# SI24r1.net
KiCad netlist of a schematic drawn in Altium Designer
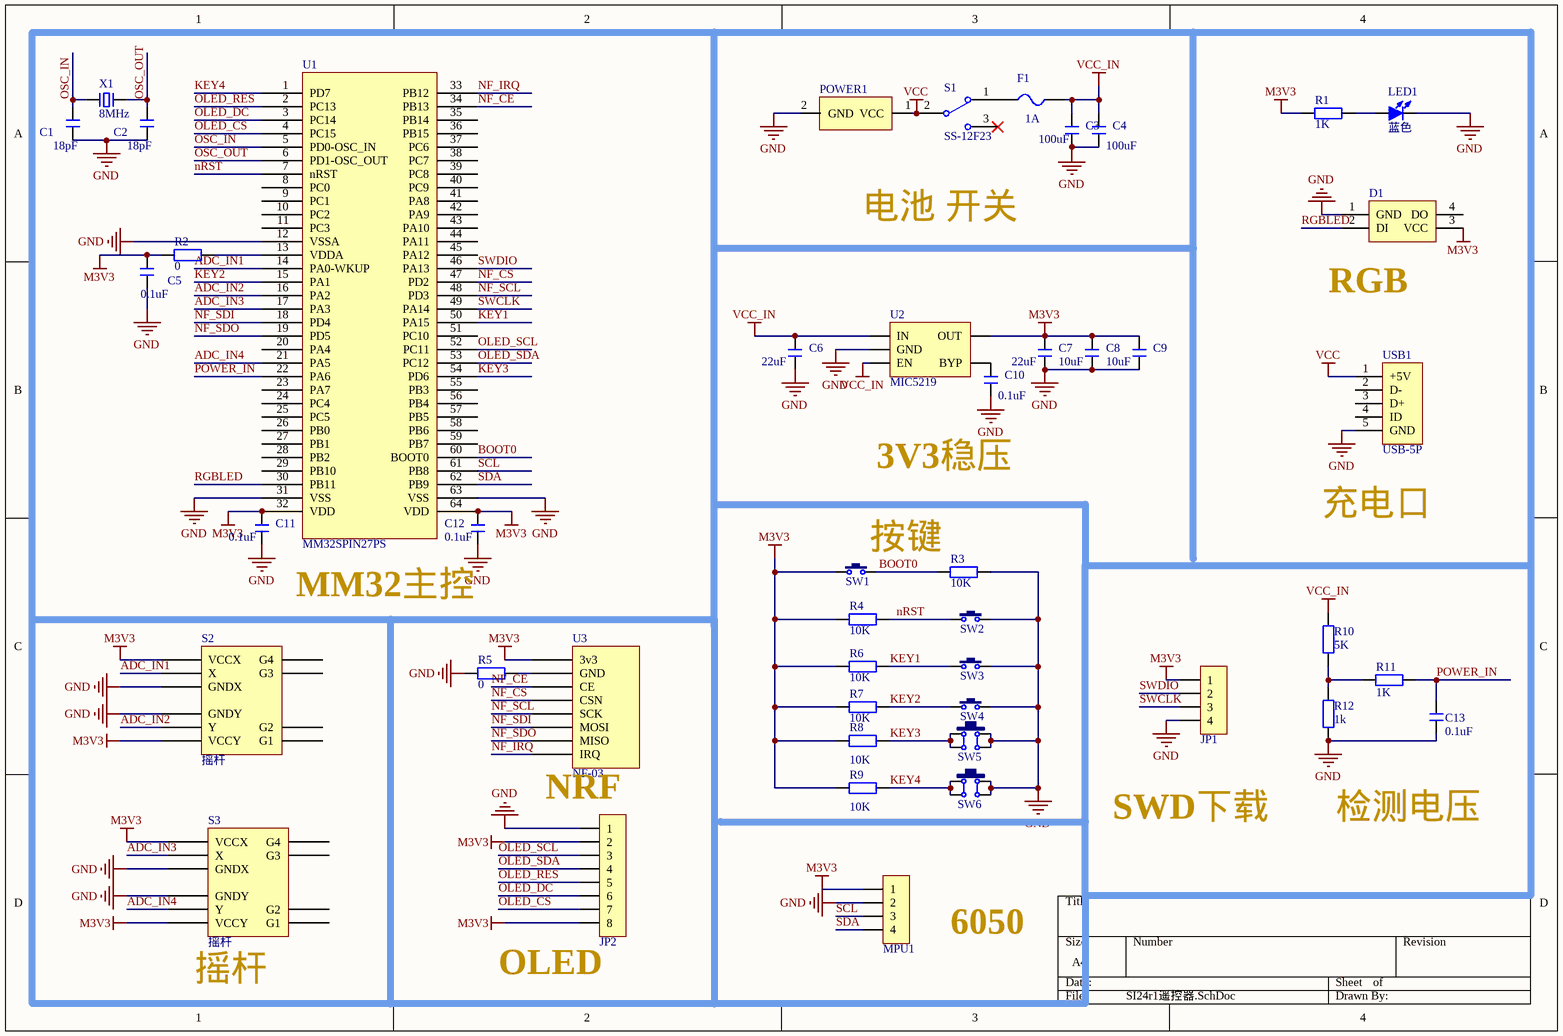
[diagram p0: SI24r1遥控器.SchDoc]

(export (version "E")
  (design (tool "Eeschema 10.0.6"))
  (components
    (comp (ref "C1")
      (value "18pF")
      (footprint "C 0805_M")
      (description "贴片电容")
      (libsource (lib "0.1 - 电阻-电容-电感") (part "C"))
    )
    (comp (ref "C2")
      (value "18pF")
      (footprint "C 0805_M")
      (description "贴片电容")
      (libsource (lib "0.1 - 电阻-电容-电感") (part "C"))
    )
    (comp (ref "C3")
      (value "100uF")
      (footprint "C 0805_M")
      (description "贴片电容")
      (libsource (lib "0.1 - 电阻-电容-电感") (part "C"))
    )
    (comp (ref "C4")
      (value "100uF")
      (footprint "C 0805_M")
      (description "贴片电容")
      (libsource (lib "0.1 - 电阻-电容-电感") (part "C"))
    )
    (comp (ref "C5")
      (value "0.1uF")
      (footprint "C 0805_M")
      (description "贴片电容")
      (libsource (lib "0.1 - 电阻-电容-电感") (part "C"))
    )
    (comp (ref "C6")
      (value "22uF")
      (footprint "C 0805_M")
      (description "贴片电容")
      (libsource (lib "0.1 - 电阻-电容-电感") (part "C"))
    )
    (comp (ref "C7")
      (value "22uF")
      (footprint "C 0805_M")
      (description "贴片电容")
      (libsource (lib "0.1 - 电阻-电容-电感") (part "C"))
    )
    (comp (ref "C8")
      (value "10uF")
      (footprint "C 0805_M")
      (description "贴片电容")
      (libsource (lib "0.1 - 电阻-电容-电感") (part "C"))
    )
    (comp (ref "C9")
      (value "10uF")
      (footprint "C 0805_M")
      (description "贴片电容")
      (libsource (lib "0.1 - 电阻-电容-电感") (part "C"))
    )
    (comp (ref "C10")
      (value "0.1uF")
      (footprint "C 0805_M")
      (description "贴片电容")
      (libsource (lib "0.1 - 电阻-电容-电感") (part "C"))
    )
    (comp (ref "C11")
      (value "0.1uF")
      (footprint "C 0805_M")
      (description "贴片电容")
      (libsource (lib "0.1 - 电阻-电容-电感") (part "C"))
    )
    (comp (ref "C12")
      (value "0.1uF")
      (footprint "C 0805_M")
      (description "贴片电容")
      (libsource (lib "0.1 - 电阻-电容-电感") (part "C"))
    )
    (comp (ref "C13")
      (value "0.1uF")
      (footprint "C 0805_M")
      (description "贴片电容")
      (libsource (lib "0.1 - 电阻-电容-电感") (part "C"))
    )
    (comp (ref "D1")
      (value "P923D")
      (footprint "RGB_LED_5050")
      (fields (field (name "PUBLISHER") "mazhongwei"))
      (libsource (lib "RoboFly") (part "P923D"))
    )
    (comp (ref "F1")
      (value "1A")
      (footprint "FU 0805")
      (description "贴片保险丝")
      (fields (field (name "版权归属") "源创客"))
      (libsource (lib "2.0 - 保险丝-晶振-光耦") (part "FU"))
    )
    (comp (ref "JP1")
      (value "HDR-1X4")
      (footprint "XH2.54-WI-4P")
      (description "4P接插件")
      (fields (field (name "版权归属") "封装库来自淘宝 ID：黄晶宝石"))
      (libsource (lib "5.3 - 接插件-脚距2.54 (100mil) ") (part "Header 4"))
    )
    (comp (ref "JP2")
      (value "HDR-1X8")
      (footprint "IPS")
      (description "8P接插件")
      (fields (field (name "版权归属") "封装库来自淘宝 ID：黄晶宝石"))
      (libsource (lib "5.3 - 接插件-脚距2.54 (100mil) ") (part "Header 8"))
    )
    (comp (ref "LED1")
      (value "蓝色")
      (footprint "LED 0805B")
      (description "贴片LED")
      (fields (field (name "版权归属") "封装库来自淘宝 ID：黄晶宝石"))
      (libsource (lib "0.3 - LED发光二极管") (part "LED-SMD"))
    )
    (comp (ref "MPU1")
      (value "HDR-1X4")
      (footprint "HDR2.54-LI-4P")
      (description "4P接插件")
      (fields (field (name "版权归属") "封装库来自淘宝 ID：黄晶宝石"))
      (libsource (lib "5.3 - 接插件-脚距2.54 (100mil) ") (part "Header 4"))
    )
    (comp (ref "POWER1") (value "~") (footprint "XH2.54-LI-2P") (libsource (lib "原理图库") (part "T槽")))
    (comp (ref "R1")
      (value "1K")
      (footprint "R 0805_M")
      (description "Resistor")
      (fields (field (name "Comment") "Res2") (field (name "PUBLISHER") "Altium Limited"))
      (libsource (lib "") (part "Res2_1"))
    )
    (comp (ref "R2") (value "0") (footprint "R 0805_M") (libsource (lib "") (part "RES_1")))
    (comp (ref "R3") (value "10K") (footprint "R 0805_M") (libsource (lib "飞思卡尔") (part "RES")))
    (comp (ref "R4") (value "10K") (footprint "R 0805_M") (libsource (lib "飞思卡尔") (part "RES")))
    (comp (ref "R5") (value "0") (footprint "R 0805_M") (libsource (lib "") (part "RES_1")))
    (comp (ref "R6") (value "10K") (footprint "R 0805_M") (libsource (lib "飞思卡尔") (part "RES")))
    (comp (ref "R7") (value "10K") (footprint "R 0805_M") (libsource (lib "飞思卡尔") (part "RES")))
    (comp (ref "R8") (value "10K") (footprint "R 0805_M") (libsource (lib "飞思卡尔") (part "RES")))
    (comp (ref "R9") (value "10K") (footprint "R 0805_M") (libsource (lib "飞思卡尔") (part "RES")))
    (comp (ref "R10")
      (value "5K")
      (footprint "R 0805_M")
      (description "Resistor")
      (fields (field (name "Comment") "Res2") (field (name "PUBLISHER") "Altium Limited"))
      (libsource (lib "双电机节能车主板原理图库") (part "Res2"))
    )
    (comp (ref "R11")
      (value "1K")
      (footprint "R 0805_M")
      (description "Resistor")
      (fields (field (name "Comment") "Res2") (field (name "PUBLISHER") "Altium Limited"))
      (libsource (lib "") (part "Res2_1"))
    )
    (comp (ref "R12")
      (value "1k")
      (footprint "R 0805_M")
      (description "Resistor")
      (fields (field (name "Comment") "Res2") (field (name "PUBLISHER") "Altium Limited"))
      (libsource (lib "双电机节能车主板原理图库") (part "Res2"))
    )
    (comp (ref "S1")
      (value "SS-12F23")
      (footprint "SS-12D10")
      (description "1路波动开关")
      (fields (field (name "版权归属") "封装库来自淘宝 ID：黄晶宝石"))
      (libsource (lib "0.7 - 常用按键-开关") (part "SSW-1P"))
    )
    (comp (ref "S2") (value "摇杆") (footprint "3D161摇杆") (libsource (lib "摇杆") (part "摇杆")))
    (comp (ref "S3") (value "摇杆") (footprint "3D161摇杆") (libsource (lib "摇杆") (part "摇杆")))
    (comp (ref "SW1")
      (value "3x6x5")
      (footprint "TSW SMD-3*6*2.5")
      (description "3x6轻触开关")
      (fields (field (name "版权归属") "封装库来自淘宝 ID：黄晶宝石"))
      (libsource (lib "0.7 - 常用按键-开关") (part "TSW 3x6"))
    )
    (comp (ref "SW2")
      (value "3x6x5")
      (footprint "TSW SMD-3*6*2.5")
      (description "3x6轻触开关")
      (fields (field (name "版权归属") "封装库来自淘宝 ID：黄晶宝石"))
      (libsource (lib "0.7 - 常用按键-开关") (part "TSW 3x6"))
    )
    (comp (ref "SW3")
      (value "6x6x5")
      (footprint "TSW DIP-6*6*7_V")
      (description "侧按直插6x6轻触开关")
      (fields (field (name "版权归属") "封装库来自淘宝 ID：黄晶宝石"))
      (libsource (lib "0.7 - 常用按键-开关") (part "TSW DIP-6x6_V"))
    )
    (comp (ref "SW4")
      (value "6x6x5")
      (footprint "TSW DIP-6*6*7_V")
      (description "侧按直插6x6轻触开关")
      (fields (field (name "版权归属") "封装库来自淘宝 ID：黄晶宝石"))
      (libsource (lib "0.7 - 常用按键-开关") (part "TSW DIP-6x6_V"))
    )
    (comp (ref "SW5")
      (value "6x6x5")
      (footprint "TSW DIP-6*6*6")
      (description "直插6x6轻触开关")
      (fields (field (name "版权归属") "封装库来自淘宝 ID：黄晶宝石"))
      (libsource (lib "0.7 - 常用按键-开关") (part "TSW DIP-6x6"))
    )
    (comp (ref "SW6")
      (value "6x6x5")
      (footprint "TSW DIP-6*6*6")
      (description "直插6x6轻触开关")
      (fields (field (name "版权归属") "封装库来自淘宝 ID：黄晶宝石"))
      (libsource (lib "0.7 - 常用按键-开关") (part "TSW DIP-6x6"))
    )
    (comp (ref "U1")
      (value "MM32SPIN27PS")
      (footprint "LQFP64 10x10_M")
      (libsource (lib "STC智能车") (part "MM32SPIN27PS"))
    )
    (comp (ref "U2") (value "MIC5219") (footprint "SOT23-5M") (libsource (lib "TI") (part "MIC5219")))
    (comp (ref "U3") (value "NF-03") (footprint "NF-03") (libsource (lib "摇杆") (part "NF-03")))
    (comp (ref "USB1")
      (value "USB-5P")
      (footprint "USB-MICRO_A")
      (description "微型USB母座")
      (libsource (lib "0.8 - 网口-音频插座") (part "USB-5P"))
    )
    (comp (ref "X1")
      (value "8MHz")
      (footprint "OSC 5032-2P")
      (description "2脚无源脚晶振")
      (fields (field (name "版权归属") "源创客"))
      (libsource (lib "2.0 - 保险丝-晶振-光耦") (part "XTAL-2P"))
    )
  )
  (nets
    (net (code "1") (name "/ADC_IN1") (class "Default")
      (node (ref "S2") (pin "2") (pinfunction "X_2") (pintype "passive"))
      (node (ref "U1") (pin "14") (pinfunction "PA0-WKUP_14") (pintype "passive"))
    )
    (net (code "2") (name "/ADC_IN2") (class "Default")
      (node (ref "S2") (pin "5") (pinfunction "Y_5") (pintype "passive"))
      (node (ref "U1") (pin "16") (pinfunction "PA2_16") (pintype "passive"))
    )
    (net (code "3") (name "/ADC_IN3") (class "Default")
      (node (ref "S3") (pin "2") (pinfunction "X_2") (pintype "passive"))
      (node (ref "U1") (pin "17") (pinfunction "PA3_17") (pintype "passive"))
    )
    (net (code "4") (name "/ADC_IN4") (class "Default")
      (node (ref "S3") (pin "5") (pinfunction "Y_5") (pintype "passive"))
      (node (ref "U1") (pin "21") (pinfunction "PA5_21") (pintype "passive"))
    )
    (net (code "5") (name "/BOOT0") (class "Default")
      (node (ref "R3") (pin "1") (pinfunction "1_1") (pintype "passive"))
      (node (ref "SW1") (pin "2") (pinfunction "2_2") (pintype "passive"))
      (node (ref "U1") (pin "60") (pinfunction "BOOT0_60") (pintype "passive"))
    )
    (net (code "6") (name "/KEY1") (class "Default")
      (node (ref "R6") (pin "2") (pinfunction "2_2") (pintype "passive"))
      (node (ref "SW3") (pin "1") (pinfunction "1_1") (pintype "passive"))
      (node (ref "U1") (pin "50") (pinfunction "PA15_50") (pintype "passive"))
    )
    (net (code "7") (name "/KEY2") (class "Default")
      (node (ref "R7") (pin "2") (pinfunction "2_2") (pintype "passive"))
      (node (ref "SW4") (pin "1") (pinfunction "1_1") (pintype "passive"))
      (node (ref "U1") (pin "15") (pinfunction "PA1_15") (pintype "passive"))
    )
    (net (code "8") (name "/KEY3") (class "Default")
      (node (ref "R8") (pin "2") (pinfunction "2_2") (pintype "passive"))
      (node (ref "SW5") (pin "1") (pinfunction "1_1") (pintype "passive"))
      (node (ref "SW5") (pin "4") (pinfunction "4_4") (pintype "passive"))
      (node (ref "U1") (pin "54") (pinfunction "PD6_54") (pintype "passive"))
    )
    (net (code "9") (name "/KEY4") (class "Default")
      (node (ref "R9") (pin "2") (pinfunction "2_2") (pintype "passive"))
      (node (ref "SW6") (pin "1") (pinfunction "1_1") (pintype "passive"))
      (node (ref "SW6") (pin "4") (pinfunction "4_4") (pintype "passive"))
      (node (ref "U1") (pin "1") (pinfunction "PD7_1") (pintype "passive"))
    )
    (net (code "10") (name "/NF_CE") (class "Default")
      (node (ref "U1") (pin "34") (pinfunction "PB13_34") (pintype "passive"))
      (node (ref "U3") (pin "3") (pinfunction "CE_3") (pintype "passive"))
    )
    (net (code "11") (name "/NF_CS") (class "Default")
      (node (ref "U1") (pin "47") (pinfunction "PD2_47") (pintype "passive"))
      (node (ref "U3") (pin "4") (pinfunction "CSN_4") (pintype "passive"))
    )
    (net (code "12") (name "/NF_IRQ") (class "Default")
      (node (ref "U1") (pin "33") (pinfunction "PB12_33") (pintype "passive"))
      (node (ref "U3") (pin "8") (pinfunction "IRQ_8") (pintype "passive"))
    )
    (net (code "13") (name "/NF_SCL") (class "Default")
      (node (ref "U1") (pin "48") (pinfunction "PD3_48") (pintype "passive"))
      (node (ref "U3") (pin "5") (pinfunction "SCK_5") (pintype "passive"))
    )
    (net (code "14") (name "/NF_SDI") (class "Default")
      (node (ref "U1") (pin "18") (pinfunction "PD4_18") (pintype "passive"))
      (node (ref "U3") (pin "6") (pinfunction "MOSI_6") (pintype "passive"))
    )
    (net (code "15") (name "/NF_SDO") (class "Default")
      (node (ref "U1") (pin "19") (pinfunction "PD5_19") (pintype "passive"))
      (node (ref "U3") (pin "7") (pinfunction "MISO_7") (pintype "passive"))
    )
    (net (code "16") (name "/OLED_CS") (class "Default")
      (node (ref "JP2") (pin "7") (pinfunction "7_7") (pintype "passive"))
      (node (ref "U1") (pin "4") (pinfunction "PC15_4") (pintype "passive"))
    )
    (net (code "17") (name "/OLED_DC") (class "Default")
      (node (ref "JP2") (pin "6") (pinfunction "6_6") (pintype "passive"))
      (node (ref "U1") (pin "3") (pinfunction "PC14_3") (pintype "passive"))
    )
    (net (code "18") (name "/OLED_RES") (class "Default")
      (node (ref "JP2") (pin "5") (pinfunction "5_5") (pintype "passive"))
      (node (ref "U1") (pin "2") (pinfunction "PC13_2") (pintype "passive"))
    )
    (net (code "19") (name "/OLED_SCL") (class "Default")
      (node (ref "JP2") (pin "3") (pinfunction "3_3") (pintype "passive"))
      (node (ref "U1") (pin "52") (pinfunction "PC11_52") (pintype "passive"))
    )
    (net (code "20") (name "/OLED_SDA") (class "Default")
      (node (ref "JP2") (pin "4") (pinfunction "4_4") (pintype "passive"))
      (node (ref "U1") (pin "53") (pinfunction "PC12_53") (pintype "passive"))
    )
    (net (code "21") (name "/OSC_IN") (class "Default")
      (node (ref "C1") (pin "2") (pinfunction "2_2") (pintype "passive"))
      (node (ref "U1") (pin "5") (pinfunction "PD0-OSC_IN_5") (pintype "passive"))
      (node (ref "X1") (pin "1") (pinfunction "1_1") (pintype "passive"))
    )
    (net (code "22") (name "/OSC_OUT") (class "Default")
      (node (ref "C2") (pin "2") (pinfunction "2_2") (pintype "passive"))
      (node (ref "U1") (pin "6") (pinfunction "PD1-OSC_OUT_6") (pintype "passive"))
      (node (ref "X1") (pin "2") (pinfunction "2_2") (pintype "passive"))
    )
    (net (code "23") (name "/POWER_IN") (class "Default")
      (node (ref "C13") (pin "2") (pinfunction "2_2") (pintype "passive"))
      (node (ref "R11") (pin "1") (pinfunction "1_1") (pintype "passive"))
      (node (ref "U1") (pin "22") (pinfunction "PA6_22") (pintype "passive"))
    )
    (net (code "24") (name "/RGBLED") (class "Default")
      (node (ref "D1") (pin "2") (pinfunction "DI_2") (pintype "passive"))
      (node (ref "U1") (pin "30") (pinfunction "PB11_30") (pintype "passive"))
    )
    (net (code "25") (name "/SCL") (class "Default")
      (node (ref "MPU1") (pin "3") (pinfunction "3_3") (pintype "passive"))
      (node (ref "U1") (pin "61") (pinfunction "PB8_61") (pintype "passive"))
    )
    (net (code "26") (name "/SDA") (class "Default")
      (node (ref "MPU1") (pin "4") (pinfunction "4_4") (pintype "passive"))
      (node (ref "U1") (pin "62") (pinfunction "PB9_62") (pintype "passive"))
    )
    (net (code "27") (name "/SWCLK") (class "Default")
      (node (ref "JP1") (pin "3") (pinfunction "3_3") (pintype "passive"))
      (node (ref "U1") (pin "49") (pinfunction "PA14_49") (pintype "passive"))
    )
    (net (code "28") (name "/SWDIO") (class "Default")
      (node (ref "JP1") (pin "2") (pinfunction "2_2") (pintype "passive"))
      (node (ref "U1") (pin "46") (pinfunction "PA13_46") (pintype "passive"))
    )
    (net (code "29") (name "/nRST") (class "Default")
      (node (ref "R4") (pin "2") (pinfunction "2_2") (pintype "passive"))
      (node (ref "SW2") (pin "1") (pinfunction "1_1") (pintype "passive"))
      (node (ref "U1") (pin "7") (pinfunction "nRST_7") (pintype "passive"))
    )
    (net (code "30") (name "GND") (class "Default")
      (node (ref "C1") (pin "1") (pinfunction "1_1") (pintype "passive"))
      (node (ref "C10") (pin "1") (pinfunction "1_1") (pintype "passive"))
      (node (ref "C11") (pin "1") (pinfunction "1_1") (pintype "passive"))
      (node (ref "C12") (pin "1") (pinfunction "1_1") (pintype "passive"))
      (node (ref "C13") (pin "1") (pinfunction "1_1") (pintype "passive"))
      (node (ref "C2") (pin "1") (pinfunction "1_1") (pintype "passive"))
      (node (ref "C3") (pin "1") (pinfunction "1_1") (pintype "passive"))
      (node (ref "C4") (pin "1") (pinfunction "1_1") (pintype "passive"))
      (node (ref "C5") (pin "1") (pinfunction "1_1") (pintype "passive"))
      (node (ref "C6") (pin "1") (pinfunction "1_1") (pintype "passive"))
      (node (ref "C7") (pin "1") (pinfunction "1_1") (pintype "passive"))
      (node (ref "C8") (pin "1") (pinfunction "1_1") (pintype "passive"))
      (node (ref "C9") (pin "1") (pinfunction "1_1") (pintype "passive"))
      (node (ref "D1") (pin "1") (pinfunction "GND_1") (pintype "passive"))
      (node (ref "JP1") (pin "4") (pinfunction "4_4") (pintype "passive"))
      (node (ref "JP2") (pin "1") (pinfunction "1_1") (pintype "passive"))
      (node (ref "LED1") (pin "2") (pinfunction "K_2") (pintype "passive"))
      (node (ref "MPU1") (pin "2") (pinfunction "2_2") (pintype "passive"))
      (node (ref "POWER1") (pin "2") (pinfunction "GND_2") (pintype "passive"))
      (node (ref "R12") (pin "1") (pinfunction "1_1") (pintype "passive"))
      (node (ref "R3") (pin "2") (pinfunction "2_2") (pintype "passive"))
      (node (ref "R5") (pin "2") (pinfunction "2_2") (pintype "passive"))
      (node (ref "S2") (pin "3") (pinfunction "GNDX_3") (pintype "passive"))
      (node (ref "S2") (pin "4") (pinfunction "GNDY_4") (pintype "passive"))
      (node (ref "S3") (pin "3") (pinfunction "GNDX_3") (pintype "passive"))
      (node (ref "S3") (pin "4") (pinfunction "GNDY_4") (pintype "passive"))
      (node (ref "SW2") (pin "2") (pinfunction "2_2") (pintype "passive"))
      (node (ref "SW3") (pin "2") (pinfunction "2_2") (pintype "passive"))
      (node (ref "SW4") (pin "2") (pinfunction "2_2") (pintype "passive"))
      (node (ref "SW5") (pin "2") (pinfunction "2_2") (pintype "passive"))
      (node (ref "SW5") (pin "3") (pinfunction "3_3") (pintype "passive"))
      (node (ref "SW6") (pin "2") (pinfunction "2_2") (pintype "passive"))
      (node (ref "SW6") (pin "3") (pinfunction "3_3") (pintype "passive"))
      (node (ref "U1") (pin "12") (pinfunction "VSSA_12") (pintype "passive"))
      (node (ref "U1") (pin "31") (pinfunction "VSS_31") (pintype "passive"))
      (node (ref "U1") (pin "63") (pinfunction "VSS_63") (pintype "passive"))
      (node (ref "U2") (pin "2") (pinfunction "GND_2") (pintype "passive"))
      (node (ref "USB1") (pin "5") (pinfunction "GND_5") (pintype "passive"))
    )
    (net (code "31") (name "M3V3") (class "Default")
      (node (ref "C11") (pin "2") (pinfunction "2_2") (pintype "passive"))
      (node (ref "C12") (pin "2") (pinfunction "2_2") (pintype "passive"))
      (node (ref "C5") (pin "2") (pinfunction "2_2") (pintype "passive"))
      (node (ref "C7") (pin "2") (pinfunction "2_2") (pintype "passive"))
      (node (ref "C8") (pin "2") (pinfunction "2_2") (pintype "passive"))
      (node (ref "C9") (pin "2") (pinfunction "2_2") (pintype "passive"))
      (node (ref "D1") (pin "3") (pinfunction "VCC_3") (pintype "passive"))
      (node (ref "JP1") (pin "1") (pinfunction "1_1") (pintype "passive"))
      (node (ref "JP2") (pin "2") (pinfunction "2_2") (pintype "passive"))
      (node (ref "JP2") (pin "8") (pinfunction "8_8") (pintype "passive"))
      (node (ref "MPU1") (pin "1") (pinfunction "1_1") (pintype "passive"))
      (node (ref "R1") (pin "2") (pinfunction "2_2") (pintype "passive"))
      (node (ref "R2") (pin "2") (pinfunction "2_2") (pintype "passive"))
      (node (ref "R4") (pin "1") (pinfunction "1_1") (pintype "passive"))
      (node (ref "R6") (pin "1") (pinfunction "1_1") (pintype "passive"))
      (node (ref "R7") (pin "1") (pinfunction "1_1") (pintype "passive"))
      (node (ref "R8") (pin "1") (pinfunction "1_1") (pintype "passive"))
      (node (ref "R9") (pin "1") (pinfunction "1_1") (pintype "passive"))
      (node (ref "S2") (pin "1") (pinfunction "VCCX_1") (pintype "passive"))
      (node (ref "S2") (pin "6") (pinfunction "VCCY_6") (pintype "passive"))
      (node (ref "S3") (pin "1") (pinfunction "VCCX_1") (pintype "passive"))
      (node (ref "S3") (pin "6") (pinfunction "VCCY_6") (pintype "passive"))
      (node (ref "SW1") (pin "1") (pinfunction "1_1") (pintype "passive"))
      (node (ref "U1") (pin "32") (pinfunction "VDD_32") (pintype "passive"))
      (node (ref "U1") (pin "64") (pinfunction "VDD_64") (pintype "passive"))
      (node (ref "U2") (pin "5") (pinfunction "OUT_5") (pintype "passive"))
      (node (ref "U3") (pin "1") (pinfunction "3v3_1") (pintype "passive"))
    )
    (net (code "32") (name "Net-(F1-Pad1)") (class "Default")
      (node (ref "F1") (pin "1") (pinfunction "1_1") (pintype "passive"))
      (node (ref "S1") (pin "1") (pinfunction "1_1") (pintype "passive"))
    )
    (net (code "33") (name "Net-(LED1-A)") (class "Default")
      (node (ref "LED1") (pin "1") (pinfunction "A_1") (pintype "passive"))
      (node (ref "R1") (pin "1") (pinfunction "1_1") (pintype "passive"))
    )
    (net (code "34") (name "Net-(R10-Pad1)") (class "Default")
      (node (ref "R10") (pin "1") (pinfunction "1_1") (pintype "passive"))
      (node (ref "R11") (pin "2") (pinfunction "2_2") (pintype "passive"))
      (node (ref "R12") (pin "2") (pinfunction "2_2") (pintype "passive"))
    )
    (net (code "35") (name "Net-(U1-VDDA)") (class "Default")
      (node (ref "R2") (pin "1") (pinfunction "1_1") (pintype "passive"))
      (node (ref "U1") (pin "13") (pinfunction "VDDA_13") (pintype "passive"))
    )
    (net (code "36") (name "Net-(U2-BYP)") (class "Default")
      (node (ref "C10") (pin "2") (pinfunction "2_2") (pintype "passive"))
      (node (ref "U2") (pin "4") (pinfunction "BYP_4") (pintype "passive"))
    )
    (net (code "37") (name "Net-(U3-GND)") (class "Default")
      (node (ref "R5") (pin "1") (pinfunction "1_1") (pintype "passive"))
      (node (ref "U3") (pin "2") (pinfunction "GND_2") (pintype "passive"))
    )
    (net (code "38") (name "VCC") (class "Default")
      (node (ref "POWER1") (pin "1") (pinfunction "VCC_1") (pintype "passive"))
      (node (ref "S1") (pin "2") (pinfunction "2_2") (pintype "passive"))
      (node (ref "USB1") (pin "1") (pinfunction "+5V_1") (pintype "passive"))
    )
    (net (code "39") (name "VCC_IN") (class "Default")
      (node (ref "C3") (pin "2") (pinfunction "2_2") (pintype "passive"))
      (node (ref "C4") (pin "2") (pinfunction "2_2") (pintype "passive"))
      (node (ref "C6") (pin "2") (pinfunction "2_2") (pintype "passive"))
      (node (ref "F1") (pin "2") (pinfunction "2_2") (pintype "passive"))
      (node (ref "R10") (pin "2") (pinfunction "2_2") (pintype "passive"))
      (node (ref "U2") (pin "1") (pinfunction "IN_1") (pintype "passive"))
      (node (ref "U2") (pin "3") (pinfunction "EN_3") (pintype "passive"))
    )
    (net (code "40") (name "unconnected-(D1-DO-Pad4)") (class "Default")
      (node (ref "D1") (pin "4") (pinfunction "DO_4") (pintype "passive"))
    )
    (net (code "41") (name "unconnected-(S1-Pad3)") (class "Default")
      (node (ref "S1") (pin "3") (pinfunction "3_3") (pintype "passive+no_connect"))
    )
    (net (code "42") (name "unconnected-(S2-G1-Pad7)") (class "Default")
      (node (ref "S2") (pin "7") (pinfunction "G1_7") (pintype "passive"))
    )
    (net (code "43") (name "unconnected-(S2-G2-Pad8)") (class "Default")
      (node (ref "S2") (pin "8") (pinfunction "G2_8") (pintype "passive"))
    )
    (net (code "44") (name "unconnected-(S2-G3-Pad9)") (class "Default")
      (node (ref "S2") (pin "9") (pinfunction "G3_9") (pintype "passive"))
    )
    (net (code "45") (name "unconnected-(S2-G4-Pad10)") (class "Default")
      (node (ref "S2") (pin "10") (pinfunction "G4_10") (pintype "passive"))
    )
    (net (code "46") (name "unconnected-(S3-G1-Pad7)") (class "Default")
      (node (ref "S3") (pin "7") (pinfunction "G1_7") (pintype "passive"))
    )
    (net (code "47") (name "unconnected-(S3-G2-Pad8)") (class "Default")
      (node (ref "S3") (pin "8") (pinfunction "G2_8") (pintype "passive"))
    )
    (net (code "48") (name "unconnected-(S3-G3-Pad9)") (class "Default")
      (node (ref "S3") (pin "9") (pinfunction "G3_9") (pintype "passive"))
    )
    (net (code "49") (name "unconnected-(S3-G4-Pad10)") (class "Default")
      (node (ref "S3") (pin "10") (pinfunction "G4_10") (pintype "passive"))
    )
    (net (code "50") (name "unconnected-(U1-PA4-Pad20)") (class "Default")
      (node (ref "U1") (pin "20") (pinfunction "PA4_20") (pintype "passive"))
    )
    (net (code "51") (name "unconnected-(U1-PA7-Pad23)") (class "Default")
      (node (ref "U1") (pin "23") (pinfunction "PA7_23") (pintype "passive"))
    )
    (net (code "52") (name "unconnected-(U1-PA8-Pad41)") (class "Default")
      (node (ref "U1") (pin "41") (pinfunction "PA8_41") (pintype "passive"))
    )
    (net (code "53") (name "unconnected-(U1-PA9-Pad42)") (class "Default")
      (node (ref "U1") (pin "42") (pinfunction "PA9_42") (pintype "passive"))
    )
    (net (code "54") (name "unconnected-(U1-PA10-Pad43)") (class "Default")
      (node (ref "U1") (pin "43") (pinfunction "PA10_43") (pintype "passive"))
    )
    (net (code "55") (name "unconnected-(U1-PA11-Pad44)") (class "Default")
      (node (ref "U1") (pin "44") (pinfunction "PA11_44") (pintype "passive"))
    )
    (net (code "56") (name "unconnected-(U1-PA12-Pad45)") (class "Default")
      (node (ref "U1") (pin "45") (pinfunction "PA12_45") (pintype "passive"))
    )
    (net (code "57") (name "unconnected-(U1-PB0-Pad26)") (class "Default")
      (node (ref "U1") (pin "26") (pinfunction "PB0_26") (pintype "passive"))
    )
    (net (code "58") (name "unconnected-(U1-PB1-Pad27)") (class "Default")
      (node (ref "U1") (pin "27") (pinfunction "PB1_27") (pintype "passive"))
    )
    (net (code "59") (name "unconnected-(U1-PB2-Pad28)") (class "Default")
      (node (ref "U1") (pin "28") (pinfunction "PB2_28") (pintype "passive"))
    )
    (net (code "60") (name "unconnected-(U1-PB3-Pad55)") (class "Default")
      (node (ref "U1") (pin "55") (pinfunction "PB3_55") (pintype "passive"))
    )
    (net (code "61") (name "unconnected-(U1-PB4-Pad56)") (class "Default")
      (node (ref "U1") (pin "56") (pinfunction "PB4_56") (pintype "passive"))
    )
    (net (code "62") (name "unconnected-(U1-PB5-Pad57)") (class "Default")
      (node (ref "U1") (pin "57") (pinfunction "PB5_57") (pintype "passive"))
    )
    (net (code "63") (name "unconnected-(U1-PB6-Pad58)") (class "Default")
      (node (ref "U1") (pin "58") (pinfunction "PB6_58") (pintype "passive"))
    )
    (net (code "64") (name "unconnected-(U1-PB7-Pad59)") (class "Default")
      (node (ref "U1") (pin "59") (pinfunction "PB7_59") (pintype "passive"))
    )
    (net (code "65") (name "unconnected-(U1-PB10-Pad29)") (class "Default")
      (node (ref "U1") (pin "29") (pinfunction "PB10_29") (pintype "passive"))
    )
    (net (code "66") (name "unconnected-(U1-PB14-Pad35)") (class "Default")
      (node (ref "U1") (pin "35") (pinfunction "PB14_35") (pintype "passive"))
    )
    (net (code "67") (name "unconnected-(U1-PB15-Pad36)") (class "Default")
      (node (ref "U1") (pin "36") (pinfunction "PB15_36") (pintype "passive"))
    )
    (net (code "68") (name "unconnected-(U1-PC0-Pad8)") (class "Default")
      (node (ref "U1") (pin "8") (pinfunction "PC0_8") (pintype "passive"))
    )
    (net (code "69") (name "unconnected-(U1-PC1-Pad9)") (class "Default")
      (node (ref "U1") (pin "9") (pinfunction "PC1_9") (pintype "passive"))
    )
    (net (code "70") (name "unconnected-(U1-PC2-Pad10)") (class "Default")
      (node (ref "U1") (pin "10") (pinfunction "PC2_10") (pintype "passive"))
    )
    (net (code "71") (name "unconnected-(U1-PC3-Pad11)") (class "Default")
      (node (ref "U1") (pin "11") (pinfunction "PC3_11") (pintype "passive"))
    )
    (net (code "72") (name "unconnected-(U1-PC4-Pad24)") (class "Default")
      (node (ref "U1") (pin "24") (pinfunction "PC4_24") (pintype "passive"))
    )
    (net (code "73") (name "unconnected-(U1-PC5-Pad25)") (class "Default")
      (node (ref "U1") (pin "25") (pinfunction "PC5_25") (pintype "passive"))
    )
    (net (code "74") (name "unconnected-(U1-PC6-Pad37)") (class "Default")
      (node (ref "U1") (pin "37") (pinfunction "PC6_37") (pintype "passive"))
    )
    (net (code "75") (name "unconnected-(U1-PC7-Pad38)") (class "Default")
      (node (ref "U1") (pin "38") (pinfunction "PC7_38") (pintype "passive"))
    )
    (net (code "76") (name "unconnected-(U1-PC8-Pad39)") (class "Default")
      (node (ref "U1") (pin "39") (pinfunction "PC8_39") (pintype "passive"))
    )
    (net (code "77") (name "unconnected-(U1-PC9-Pad40)") (class "Default")
      (node (ref "U1") (pin "40") (pinfunction "PC9_40") (pintype "passive"))
    )
    (net (code "78") (name "unconnected-(U1-PC10-Pad51)") (class "Default")
      (node (ref "U1") (pin "51") (pinfunction "PC10_51") (pintype "passive"))
    )
    (net (code "79") (name "unconnected-(USB1-D+-Pad3)") (class "Default")
      (node (ref "USB1") (pin "3") (pinfunction "D+_3") (pintype "passive"))
    )
    (net (code "80") (name "unconnected-(USB1-D--Pad2)") (class "Default")
      (node (ref "USB1") (pin "2") (pinfunction "D-_2") (pintype "passive"))
    )
    (net (code "81") (name "unconnected-(USB1-ID-Pad4)") (class "Default")
      (node (ref "USB1") (pin "4") (pinfunction "ID_4") (pintype "passive"))
    )
  )
)
